# FELW0JYIN238K3G.net
KiCad netlist of a schematic drawn in EAGLE
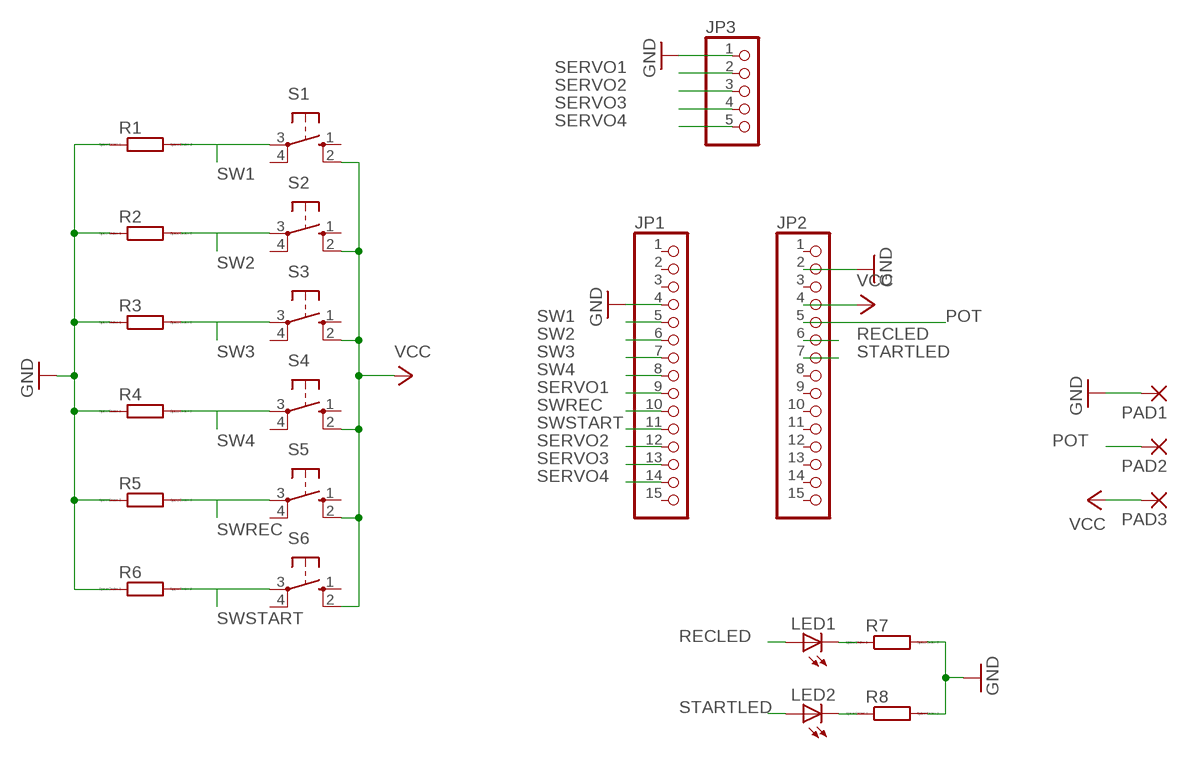
[diagram p0: schematic, sheet 1]

(export (version "E")
  (design (tool "Eeschema 10.0.6"))
  (components
    (comp (ref "JP1")
      (value "PINHD-1X15")
      (footprint "eagle-import:1X15")
      (libsource (lib "eagle-import") (part "PINHD-1X15"))
    )
    (comp (ref "JP2")
      (value "PINHD-1X15")
      (footprint "eagle-import:1X15")
      (libsource (lib "eagle-import") (part "PINHD-1X15"))
    )
    (comp (ref "JP3")
      (value "PINHD-1X5")
      (footprint "eagle-import:1X05")
      (libsource (lib "eagle-import") (part "PINHD-1X5"))
    )
    (comp (ref "LED1")
      (value "LED5MM")
      (footprint "eagle-import:LED5MM")
      (libsource (lib "eagle-import") (part "LED5MM"))
    )
    (comp (ref "LED2")
      (value "LED5MM")
      (footprint "eagle-import:LED5MM")
      (libsource (lib "eagle-import") (part "LED5MM"))
    )
    (comp (ref "PAD1")
      (value "2,54/1,0")
      (footprint "eagle-import:2,54_1,0")
      (libsource (lib "eagle-import") (part "2,54/1,0"))
    )
    (comp (ref "PAD2")
      (value "2,54/1,0")
      (footprint "eagle-import:2,54_1,0")
      (libsource (lib "eagle-import") (part "2,54/1,0"))
    )
    (comp (ref "PAD3")
      (value "2,54/1,0")
      (footprint "eagle-import:2,54_1,0")
      (libsource (lib "eagle-import") (part "2,54/1,0"))
    )
    (comp (ref "R1")
      (value "R0207/10")
      (footprint "eagle-import:0207_10")
      (libsource (lib "eagle-import") (part "R0207/10"))
    )
    (comp (ref "R2")
      (value "R0207/10")
      (footprint "eagle-import:0207_10")
      (libsource (lib "eagle-import") (part "R0207/10"))
    )
    (comp (ref "R3")
      (value "R0207/10")
      (footprint "eagle-import:0207_10")
      (libsource (lib "eagle-import") (part "R0207/10"))
    )
    (comp (ref "R4")
      (value "R0207/10")
      (footprint "eagle-import:0207_10")
      (libsource (lib "eagle-import") (part "R0207/10"))
    )
    (comp (ref "R5")
      (value "R0207/10")
      (footprint "eagle-import:0207_10")
      (libsource (lib "eagle-import") (part "R0207/10"))
    )
    (comp (ref "R6")
      (value "R0207/10")
      (footprint "eagle-import:0207_10")
      (libsource (lib "eagle-import") (part "R0207/10"))
    )
    (comp (ref "R7")
      (value "R0207/10")
      (footprint "eagle-import:0207_10")
      (libsource (lib "eagle-import") (part "R0207/10"))
    )
    (comp (ref "R8")
      (value "R0207/10")
      (footprint "eagle-import:0207_10")
      (libsource (lib "eagle-import") (part "R0207/10"))
    )
    (comp (ref "S1")
      (value "10-XX")
      (footprint "eagle-import:B3F-10XX")
      (fields (field (name "MPN") "B3F-1000"))
      (libsource (lib "eagle-import") (part "10-XX"))
    )
    (comp (ref "S2")
      (value "10-XX")
      (footprint "eagle-import:B3F-10XX")
      (fields (field (name "MPN") "B3F-1000"))
      (libsource (lib "eagle-import") (part "10-XX"))
    )
    (comp (ref "S3")
      (value "10-XX")
      (footprint "eagle-import:B3F-10XX")
      (fields (field (name "MPN") "B3F-1000"))
      (libsource (lib "eagle-import") (part "10-XX"))
    )
    (comp (ref "S4")
      (value "10-XX")
      (footprint "eagle-import:B3F-10XX")
      (fields (field (name "MPN") "B3F-1000"))
      (libsource (lib "eagle-import") (part "10-XX"))
    )
    (comp (ref "S5")
      (value "10-XX")
      (footprint "eagle-import:B3F-10XX")
      (fields (field (name "MPN") "B3F-1000"))
      (libsource (lib "eagle-import") (part "10-XX"))
    )
    (comp (ref "S6")
      (value "10-XX")
      (footprint "eagle-import:B3F-10XX")
      (fields (field (name "MPN") "B3F-1000"))
      (libsource (lib "eagle-import") (part "10-XX"))
    )
  )
  (nets
    (net (code "1") (name "/POT") (class "Default")
      (node (ref "JP2") (pin "5") (pinfunction "5_5") (pintype "passive"))
      (node (ref "PAD2") (pin "1") (pinfunction "P_1") (pintype "passive"))
    )
    (net (code "2") (name "/RECLED") (class "Default")
      (node (ref "JP2") (pin "6") (pinfunction "6_6") (pintype "passive"))
      (node (ref "LED1") (pin "A") (pinfunction "A_A") (pintype "passive"))
    )
    (net (code "3") (name "/SERVO1") (class "Default")
      (node (ref "JP1") (pin "9") (pinfunction "9_9") (pintype "passive"))
      (node (ref "JP3") (pin "2") (pinfunction "2_2") (pintype "passive"))
    )
    (net (code "4") (name "/SERVO2") (class "Default")
      (node (ref "JP1") (pin "12") (pinfunction "12_12") (pintype "passive"))
      (node (ref "JP3") (pin "3") (pinfunction "3_3") (pintype "passive"))
    )
    (net (code "5") (name "/SERVO3") (class "Default")
      (node (ref "JP1") (pin "13") (pinfunction "13_13") (pintype "passive"))
      (node (ref "JP3") (pin "4") (pinfunction "4_4") (pintype "passive"))
    )
    (net (code "6") (name "/SERVO4") (class "Default")
      (node (ref "JP1") (pin "14") (pinfunction "14_14") (pintype "passive"))
      (node (ref "JP3") (pin "5") (pinfunction "5_5") (pintype "passive"))
    )
    (net (code "7") (name "/STARTLED") (class "Default")
      (node (ref "JP2") (pin "7") (pinfunction "7_7") (pintype "passive"))
      (node (ref "LED2") (pin "A") (pinfunction "A_A") (pintype "passive"))
    )
    (net (code "8") (name "/SW1") (class "Default")
      (node (ref "JP1") (pin "5") (pinfunction "5_5") (pintype "passive"))
      (node (ref "R1") (pin "2") (pinfunction "2_2") (pintype "passive"))
      (node (ref "S1") (pin "3") (pinfunction "P_3") (pintype "passive"))
    )
    (net (code "9") (name "/SW2") (class "Default")
      (node (ref "JP1") (pin "6") (pinfunction "6_6") (pintype "passive"))
      (node (ref "R2") (pin "2") (pinfunction "2_2") (pintype "passive"))
      (node (ref "S2") (pin "3") (pinfunction "P_3") (pintype "passive"))
    )
    (net (code "10") (name "/SW3") (class "Default")
      (node (ref "JP1") (pin "7") (pinfunction "7_7") (pintype "passive"))
      (node (ref "R3") (pin "2") (pinfunction "2_2") (pintype "passive"))
      (node (ref "S3") (pin "3") (pinfunction "P_3") (pintype "passive"))
    )
    (net (code "11") (name "/SW4") (class "Default")
      (node (ref "JP1") (pin "8") (pinfunction "8_8") (pintype "passive"))
      (node (ref "R4") (pin "2") (pinfunction "2_2") (pintype "passive"))
      (node (ref "S4") (pin "3") (pinfunction "P_3") (pintype "passive"))
    )
    (net (code "12") (name "/SWREC") (class "Default")
      (node (ref "JP1") (pin "10") (pinfunction "10_10") (pintype "passive"))
      (node (ref "R5") (pin "2") (pinfunction "2_2") (pintype "passive"))
      (node (ref "S5") (pin "3") (pinfunction "P_3") (pintype "passive"))
    )
    (net (code "13") (name "/SWSTART") (class "Default")
      (node (ref "JP1") (pin "11") (pinfunction "11_11") (pintype "passive"))
      (node (ref "R6") (pin "2") (pinfunction "2_2") (pintype "passive"))
      (node (ref "S6") (pin "3") (pinfunction "P_3") (pintype "passive"))
    )
    (net (code "14") (name "GND") (class "Default")
      (node (ref "JP1") (pin "4") (pinfunction "4_4") (pintype "passive"))
      (node (ref "JP2") (pin "2") (pinfunction "2_2") (pintype "passive"))
      (node (ref "JP3") (pin "1") (pinfunction "1_1") (pintype "passive"))
      (node (ref "PAD1") (pin "1") (pinfunction "P_1") (pintype "passive"))
      (node (ref "R1") (pin "1") (pinfunction "1_1") (pintype "passive"))
      (node (ref "R2") (pin "1") (pinfunction "1_1") (pintype "passive"))
      (node (ref "R3") (pin "1") (pinfunction "1_1") (pintype "passive"))
      (node (ref "R4") (pin "1") (pinfunction "1_1") (pintype "passive"))
      (node (ref "R5") (pin "1") (pinfunction "1_1") (pintype "passive"))
      (node (ref "R6") (pin "1") (pinfunction "1_1") (pintype "passive"))
      (node (ref "R7") (pin "2") (pinfunction "2_2") (pintype "passive"))
      (node (ref "R8") (pin "2") (pinfunction "2_2") (pintype "passive"))
    )
    (net (code "15") (name "Net-(LED1-C)") (class "Default")
      (node (ref "LED1") (pin "K") (pinfunction "C_K") (pintype "passive"))
      (node (ref "R7") (pin "1") (pinfunction "1_1") (pintype "passive"))
    )
    (net (code "16") (name "Net-(LED2-C)") (class "Default")
      (node (ref "LED2") (pin "K") (pinfunction "C_K") (pintype "passive"))
      (node (ref "R8") (pin "1") (pinfunction "1_1") (pintype "passive"))
    )
    (net (code "17") (name "VCC") (class "Default")
      (node (ref "JP2") (pin "4") (pinfunction "4_4") (pintype "passive"))
      (node (ref "PAD3") (pin "1") (pinfunction "P_1") (pintype "passive"))
      (node (ref "S1") (pin "2") (pinfunction "S1_2") (pintype "passive"))
      (node (ref "S2") (pin "2") (pinfunction "S1_2") (pintype "passive"))
      (node (ref "S3") (pin "2") (pinfunction "S1_2") (pintype "passive"))
      (node (ref "S4") (pin "2") (pinfunction "S1_2") (pintype "passive"))
      (node (ref "S5") (pin "2") (pinfunction "S1_2") (pintype "passive"))
      (node (ref "S6") (pin "2") (pinfunction "S1_2") (pintype "passive"))
    )
    (net (code "18") (name "unconnected-(JP1-Pad1)") (class "Default")
      (node (ref "JP1") (pin "1") (pinfunction "1_1") (pintype "passive"))
    )
    (net (code "19") (name "unconnected-(JP1-Pad2)") (class "Default")
      (node (ref "JP1") (pin "2") (pinfunction "2_2") (pintype "passive"))
    )
    (net (code "20") (name "unconnected-(JP1-Pad3)") (class "Default")
      (node (ref "JP1") (pin "3") (pinfunction "3_3") (pintype "passive"))
    )
    (net (code "21") (name "unconnected-(JP1-Pad15)") (class "Default")
      (node (ref "JP1") (pin "15") (pinfunction "15_15") (pintype "passive"))
    )
    (net (code "22") (name "unconnected-(JP2-Pad1)") (class "Default")
      (node (ref "JP2") (pin "1") (pinfunction "1_1") (pintype "passive"))
    )
    (net (code "23") (name "unconnected-(JP2-Pad3)") (class "Default")
      (node (ref "JP2") (pin "3") (pinfunction "3_3") (pintype "passive"))
    )
    (net (code "24") (name "unconnected-(JP2-Pad8)") (class "Default")
      (node (ref "JP2") (pin "8") (pinfunction "8_8") (pintype "passive"))
    )
    (net (code "25") (name "unconnected-(JP2-Pad9)") (class "Default")
      (node (ref "JP2") (pin "9") (pinfunction "9_9") (pintype "passive"))
    )
    (net (code "26") (name "unconnected-(JP2-Pad10)") (class "Default")
      (node (ref "JP2") (pin "10") (pinfunction "10_10") (pintype "passive"))
    )
    (net (code "27") (name "unconnected-(JP2-Pad11)") (class "Default")
      (node (ref "JP2") (pin "11") (pinfunction "11_11") (pintype "passive"))
    )
    (net (code "28") (name "unconnected-(JP2-Pad12)") (class "Default")
      (node (ref "JP2") (pin "12") (pinfunction "12_12") (pintype "passive"))
    )
    (net (code "29") (name "unconnected-(JP2-Pad13)") (class "Default")
      (node (ref "JP2") (pin "13") (pinfunction "13_13") (pintype "passive"))
    )
    (net (code "30") (name "unconnected-(JP2-Pad14)") (class "Default")
      (node (ref "JP2") (pin "14") (pinfunction "14_14") (pintype "passive"))
    )
    (net (code "31") (name "unconnected-(JP2-Pad15)") (class "Default")
      (node (ref "JP2") (pin "15") (pinfunction "15_15") (pintype "passive"))
    )
    (net (code "32") (name "unconnected-(S1-P1-Pad4)") (class "Default")
      (node (ref "S1") (pin "4") (pinfunction "P1_4") (pintype "passive"))
    )
    (net (code "33") (name "unconnected-(S1-S-Pad1)") (class "Default")
      (node (ref "S1") (pin "1") (pinfunction "S_1") (pintype "passive"))
    )
    (net (code "34") (name "unconnected-(S2-P1-Pad4)") (class "Default")
      (node (ref "S2") (pin "4") (pinfunction "P1_4") (pintype "passive"))
    )
    (net (code "35") (name "unconnected-(S2-S-Pad1)") (class "Default")
      (node (ref "S2") (pin "1") (pinfunction "S_1") (pintype "passive"))
    )
    (net (code "36") (name "unconnected-(S3-P1-Pad4)") (class "Default")
      (node (ref "S3") (pin "4") (pinfunction "P1_4") (pintype "passive"))
    )
    (net (code "37") (name "unconnected-(S3-S-Pad1)") (class "Default")
      (node (ref "S3") (pin "1") (pinfunction "S_1") (pintype "passive"))
    )
    (net (code "38") (name "unconnected-(S4-P1-Pad4)") (class "Default")
      (node (ref "S4") (pin "4") (pinfunction "P1_4") (pintype "passive"))
    )
    (net (code "39") (name "unconnected-(S4-S-Pad1)") (class "Default")
      (node (ref "S4") (pin "1") (pinfunction "S_1") (pintype "passive"))
    )
    (net (code "40") (name "unconnected-(S5-P1-Pad4)") (class "Default")
      (node (ref "S5") (pin "4") (pinfunction "P1_4") (pintype "passive"))
    )
    (net (code "41") (name "unconnected-(S5-S-Pad1)") (class "Default")
      (node (ref "S5") (pin "1") (pinfunction "S_1") (pintype "passive"))
    )
    (net (code "42") (name "unconnected-(S6-P1-Pad4)") (class "Default")
      (node (ref "S6") (pin "4") (pinfunction "P1_4") (pintype "passive"))
    )
    (net (code "43") (name "unconnected-(S6-S-Pad1)") (class "Default")
      (node (ref "S6") (pin "1") (pinfunction "S_1") (pintype "passive"))
    )
  )
)
